# tarocco-v1_1.net
KiCad netlist of a schematic drawn in EAGLE
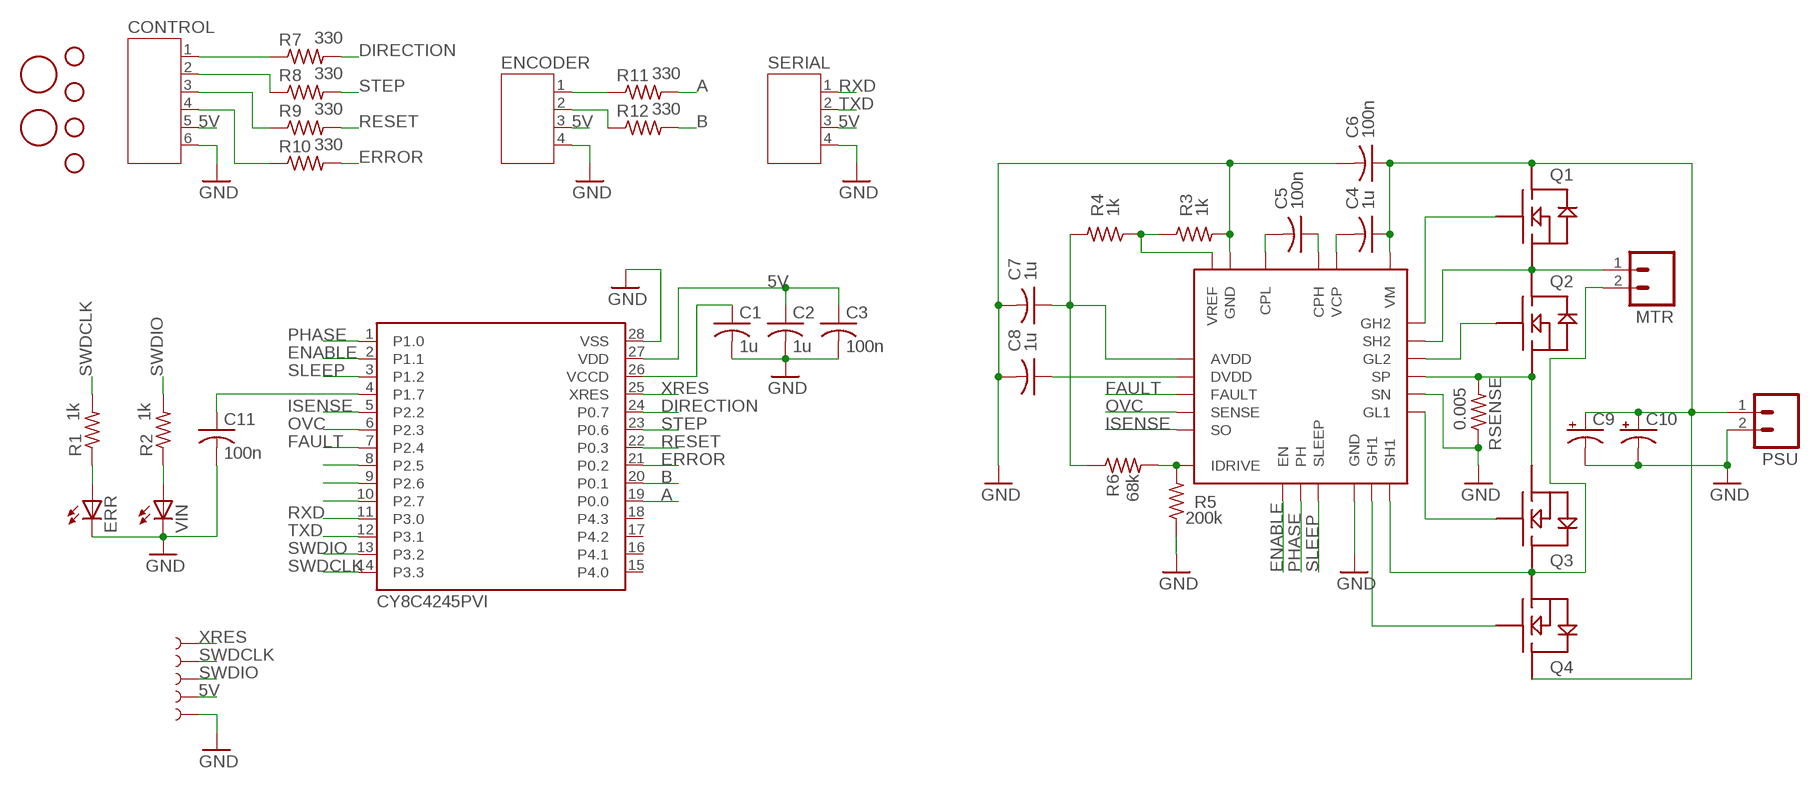
[diagram p0: schematic, sheet 1]

(export (version "E")
  (design (tool "Eeschema 10.0.6"))
  (components
    (comp (ref "8701")
      (value "DRV8701")
      (footprint "eagle-import:VQFN24")
      (libsource (lib "eagle-import") (part "DRV8701"))
    )
    (comp (ref "C1")
      (value "1u")
      (footprint "eagle-import:C0603")
      (libsource (lib "eagle-import") (part "C-USC0603"))
    )
    (comp (ref "C2")
      (value "1u")
      (footprint "eagle-import:C0603")
      (libsource (lib "eagle-import") (part "C-USC0603"))
    )
    (comp (ref "C3")
      (value "100n")
      (footprint "eagle-import:C0603")
      (libsource (lib "eagle-import") (part "C-USC0603"))
    )
    (comp (ref "C4")
      (value "1u")
      (footprint "eagle-import:C0603")
      (libsource (lib "eagle-import") (part "C-USC0603"))
    )
    (comp (ref "C5")
      (value "100n")
      (footprint "eagle-import:C0603")
      (libsource (lib "eagle-import") (part "C-USC0603"))
    )
    (comp (ref "C6")
      (value "100n")
      (footprint "eagle-import:C0603")
      (libsource (lib "eagle-import") (part "C-USC0603"))
    )
    (comp (ref "C7")
      (value "1u")
      (footprint "eagle-import:C0603")
      (libsource (lib "eagle-import") (part "C-USC0603"))
    )
    (comp (ref "C8")
      (value "1u")
      (footprint "eagle-import:C0603")
      (libsource (lib "eagle-import") (part "C-USC0603"))
    )
    (comp (ref "C9")
      (value "CPOL-USE3.5-8")
      (footprint "eagle-import:E3,5-8")
      (libsource (lib "eagle-import") (part "CPOL-USE3.5-8"))
    )
    (comp (ref "C10")
      (value "CPOL-USE3.5-8")
      (footprint "eagle-import:E3,5-8")
      (libsource (lib "eagle-import") (part "CPOL-USE3.5-8"))
    )
    (comp (ref "C11")
      (value "100n")
      (footprint "eagle-import:C0603")
      (libsource (lib "eagle-import") (part "C-USC0603"))
    )
    (comp (ref "CONTROL")
      (value "JST-PH6")
      (footprint "eagle-import:JST-PH6")
      (libsource (lib "eagle-import") (part "JST-PH6"))
    )
    (comp (ref "ENCODER")
      (value "JST-PH4")
      (footprint "eagle-import:JST-PH4")
      (libsource (lib "eagle-import") (part "JST-PH4"))
    )
    (comp (ref "ERR")
      (value "LEDCHIP-LED0603")
      (footprint "eagle-import:CHIP-LED0603")
      (libsource (lib "eagle-import") (part "LEDCHIP-LED0603"))
    )
    (comp (ref "IC1")
      (value "CY8C4545PVI")
      (footprint "eagle-import:SSOP28")
      (libsource (lib "eagle-import") (part "CY8C4545PVI"))
    )
    (comp (ref "MTR")
      (value "M023.5MM")
      (footprint "eagle-import:SCREWTERMINAL-3.5MM-2")
      (libsource (lib "eagle-import") (part "M023.5MM"))
    )
    (comp (ref "PSU")
      (value "M023.5MM")
      (footprint "eagle-import:SCREWTERMINAL-3.5MM-2")
      (libsource (lib "eagle-import") (part "M023.5MM"))
    )
    (comp (ref "Q1")
      (value "NEXFET_SINGLECSD18537NQ5A")
      (footprint "eagle-import:SON5X6")
      (libsource (lib "eagle-import") (part "NEXFET_SINGLECSD18537NQ5A"))
    )
    (comp (ref "Q2")
      (value "NEXFET_SINGLECSD18537NQ5A")
      (footprint "eagle-import:SON5X6")
      (libsource (lib "eagle-import") (part "NEXFET_SINGLECSD18537NQ5A"))
    )
    (comp (ref "Q3")
      (value "NEXFET_SINGLECSD18537NQ5A")
      (footprint "eagle-import:SON5X6")
      (libsource (lib "eagle-import") (part "NEXFET_SINGLECSD18537NQ5A"))
    )
    (comp (ref "Q4")
      (value "NEXFET_SINGLECSD18537NQ5A")
      (footprint "eagle-import:SON5X6")
      (libsource (lib "eagle-import") (part "NEXFET_SINGLECSD18537NQ5A"))
    )
    (comp (ref "R1")
      (value "1k")
      (footprint "eagle-import:R0603")
      (libsource (lib "eagle-import") (part "R-US_R0603"))
    )
    (comp (ref "R2")
      (value "1k")
      (footprint "eagle-import:R0603")
      (libsource (lib "eagle-import") (part "R-US_R0603"))
    )
    (comp (ref "R3")
      (value "1k")
      (footprint "eagle-import:R0603")
      (libsource (lib "eagle-import") (part "R-US_R0603"))
    )
    (comp (ref "R4")
      (value "1k")
      (footprint "eagle-import:R0603")
      (libsource (lib "eagle-import") (part "R-US_R0603"))
    )
    (comp (ref "R5")
      (value "200k")
      (footprint "eagle-import:R0603")
      (libsource (lib "eagle-import") (part "R-US_R0603"))
    )
    (comp (ref "R6")
      (value "68k")
      (footprint "eagle-import:R0603")
      (libsource (lib "eagle-import") (part "R-US_R0603"))
    )
    (comp (ref "R7")
      (value "330")
      (footprint "eagle-import:R0603")
      (libsource (lib "eagle-import") (part "R-US_R0603"))
    )
    (comp (ref "R8")
      (value "330")
      (footprint "eagle-import:R0603")
      (libsource (lib "eagle-import") (part "R-US_R0603"))
    )
    (comp (ref "R9")
      (value "330")
      (footprint "eagle-import:R0603")
      (libsource (lib "eagle-import") (part "R-US_R0603"))
    )
    (comp (ref "R10")
      (value "330")
      (footprint "eagle-import:R0603")
      (libsource (lib "eagle-import") (part "R-US_R0603"))
    )
    (comp (ref "R11")
      (value "330")
      (footprint "eagle-import:R0603")
      (libsource (lib "eagle-import") (part "R-US_R0603"))
    )
    (comp (ref "R12")
      (value "330")
      (footprint "eagle-import:R0603")
      (libsource (lib "eagle-import") (part "R-US_R0603"))
    )
    (comp (ref "RSENSE")
      (value "0.005")
      (footprint "eagle-import:R2512")
      (libsource (lib "eagle-import") (part "R-US_R2512"))
    )
    (comp (ref "SERIAL")
      (value "JST-PH4")
      (footprint "eagle-import:JST-PH4")
      (libsource (lib "eagle-import") (part "JST-PH4"))
    )
    (comp (ref "STANDOFF1")
      (value "STAND-OFF")
      (footprint "eagle-import:STAND-OFF")
      (libsource (lib "eagle-import") (part "STAND-OFF"))
    )
    (comp (ref "STANDOFF2")
      (value "STAND-OFF")
      (footprint "eagle-import:STAND-OFF")
      (libsource (lib "eagle-import") (part "STAND-OFF"))
    )
    (comp (ref "STANDOFF3")
      (value "STAND-OFF")
      (footprint "eagle-import:STAND-OFF")
      (libsource (lib "eagle-import") (part "STAND-OFF"))
    )
    (comp (ref "STANDOFF4")
      (value "STAND-OFF")
      (footprint "eagle-import:STAND-OFF")
      (libsource (lib "eagle-import") (part "STAND-OFF"))
    )
    (comp (ref "TP1")
      (value "TEST-POINT3X5")
      (footprint "eagle-import:PAD.03X.05")
      (libsource (lib "eagle-import") (part "TEST-POINT3X5"))
    )
    (comp (ref "TP2")
      (value "TEST-POINT3X5")
      (footprint "eagle-import:PAD.03X.05")
      (libsource (lib "eagle-import") (part "TEST-POINT3X5"))
    )
    (comp (ref "TP3")
      (value "TEST-POINT3X5")
      (footprint "eagle-import:PAD.03X.05")
      (libsource (lib "eagle-import") (part "TEST-POINT3X5"))
    )
    (comp (ref "TP4")
      (value "TEST-POINT3X5")
      (footprint "eagle-import:PAD.03X.05")
      (libsource (lib "eagle-import") (part "TEST-POINT3X5"))
    )
    (comp (ref "TP5")
      (value "TEST-POINT3X5")
      (footprint "eagle-import:PAD.03X.05")
      (libsource (lib "eagle-import") (part "TEST-POINT3X5"))
    )
    (comp (ref "U$1")
      (value "FIDUCIAL")
      (footprint "eagle-import:FIDUCIAL_1MM")
      (libsource (lib "eagle-import") (part "FIDUCIAL"))
    )
    (comp (ref "U$3")
      (value "FIDUCIAL")
      (footprint "eagle-import:FIDUCIAL_1MM")
      (libsource (lib "eagle-import") (part "FIDUCIAL"))
    )
    (comp (ref "VIN")
      (value "LEDCHIP-LED0603")
      (footprint "eagle-import:CHIP-LED0603")
      (libsource (lib "eagle-import") (part "LEDCHIP-LED0603"))
    )
  )
  (nets
    (net (code "1") (name "/5V") (class "Default")
      (node (ref "C2") (pin "1") (pinfunction "1_1") (pintype "passive"))
      (node (ref "C3") (pin "1") (pinfunction "1_1") (pintype "passive"))
      (node (ref "CONTROL") (pin "5") (pinfunction "5_5") (pintype "passive"))
      (node (ref "ENCODER") (pin "3") (pinfunction "3_3") (pintype "passive"))
      (node (ref "IC1") (pin "27") (pinfunction "VDD_27") (pintype "power_in"))
      (node (ref "SERIAL") (pin "3") (pinfunction "3_3") (pintype "passive"))
      (node (ref "TP4") (pin "P$1") (pinfunction "1_P$1") (pintype "bidirectional"))
    )
    (net (code "2") (name "/A") (class "Default")
      (node (ref "IC1") (pin "19") (pinfunction "P0.0_19") (pintype "bidirectional"))
      (node (ref "R11") (pin "2") (pinfunction "2_2") (pintype "passive"))
    )
    (net (code "3") (name "/B") (class "Default")
      (node (ref "IC1") (pin "20") (pinfunction "P0.1_20") (pintype "bidirectional"))
      (node (ref "R12") (pin "2") (pinfunction "2_2") (pintype "passive"))
    )
    (net (code "4") (name "/DIRECTION") (class "Default")
      (node (ref "IC1") (pin "24") (pinfunction "P0.7_24") (pintype "bidirectional"))
      (node (ref "R7") (pin "2") (pinfunction "2_2") (pintype "passive"))
    )
    (net (code "5") (name "/ENABLE") (class "Default")
      (node (ref "8701") (pin "EN") (pinfunction "EN_EN") (pintype "bidirectional"))
      (node (ref "IC1") (pin "2") (pinfunction "P1.1_2") (pintype "bidirectional"))
    )
    (net (code "6") (name "/ERROR") (class "Default")
      (node (ref "IC1") (pin "21") (pinfunction "P0.2_21") (pintype "bidirectional"))
      (node (ref "R10") (pin "2") (pinfunction "2_2") (pintype "passive"))
    )
    (net (code "7") (name "/FAULT") (class "Default")
      (node (ref "8701") (pin "FAULT") (pinfunction "FAULT_FAULT") (pintype "bidirectional"))
      (node (ref "IC1") (pin "7") (pinfunction "P2.4_7") (pintype "bidirectional"))
    )
    (net (code "8") (name "/ISENSE") (class "Default")
      (node (ref "8701") (pin "SO") (pinfunction "SO_SO") (pintype "bidirectional"))
      (node (ref "IC1") (pin "5") (pinfunction "P2.2_5") (pintype "bidirectional"))
    )
    (net (code "9") (name "/OVC") (class "Default")
      (node (ref "8701") (pin "SENSE") (pinfunction "SENSE_SENSE") (pintype "bidirectional"))
      (node (ref "IC1") (pin "6") (pinfunction "P2.3_6") (pintype "bidirectional"))
    )
    (net (code "10") (name "/PHASE") (class "Default")
      (node (ref "8701") (pin "PH") (pinfunction "PH_PH") (pintype "bidirectional"))
      (node (ref "IC1") (pin "1") (pinfunction "P1.0_1") (pintype "bidirectional"))
    )
    (net (code "11") (name "/RESET") (class "Default")
      (node (ref "IC1") (pin "22") (pinfunction "P0.3_22") (pintype "bidirectional"))
      (node (ref "R9") (pin "2") (pinfunction "2_2") (pintype "passive"))
    )
    (net (code "12") (name "/RXD") (class "Default")
      (node (ref "IC1") (pin "11") (pinfunction "P3.0_11") (pintype "bidirectional"))
      (node (ref "SERIAL") (pin "1") (pinfunction "1_1") (pintype "passive"))
    )
    (net (code "13") (name "/SLEEP") (class "Default")
      (node (ref "8701") (pin "SLEEP") (pinfunction "SLEEP_SLEEP") (pintype "bidirectional"))
      (node (ref "IC1") (pin "3") (pinfunction "P1.2_3") (pintype "bidirectional"))
    )
    (net (code "14") (name "/STEP") (class "Default")
      (node (ref "IC1") (pin "23") (pinfunction "P0.6_23") (pintype "bidirectional"))
      (node (ref "R8") (pin "2") (pinfunction "2_2") (pintype "passive"))
    )
    (net (code "15") (name "/SWDCLK") (class "Default")
      (node (ref "IC1") (pin "14") (pinfunction "P3.3_14") (pintype "bidirectional"))
      (node (ref "R1") (pin "2") (pinfunction "2_2") (pintype "passive"))
      (node (ref "TP2") (pin "P$1") (pinfunction "1_P$1") (pintype "bidirectional"))
    )
    (net (code "16") (name "/SWDIO") (class "Default")
      (node (ref "IC1") (pin "13") (pinfunction "P3.2_13") (pintype "bidirectional"))
      (node (ref "R2") (pin "2") (pinfunction "2_2") (pintype "passive"))
      (node (ref "TP3") (pin "P$1") (pinfunction "1_P$1") (pintype "bidirectional"))
    )
    (net (code "17") (name "/TXD") (class "Default")
      (node (ref "IC1") (pin "12") (pinfunction "P3.1_12") (pintype "bidirectional"))
      (node (ref "SERIAL") (pin "2") (pinfunction "2_2") (pintype "passive"))
    )
    (net (code "18") (name "/XRES") (class "Default")
      (node (ref "IC1") (pin "25") (pinfunction "XRES_25") (pintype "bidirectional"))
      (node (ref "TP1") (pin "P$1") (pinfunction "1_P$1") (pintype "bidirectional"))
    )
    (net (code "19") (name "GND") (class "Default")
      (node (ref "8701") (pin "GND@1") (pinfunction "GND_GND@1") (pintype "bidirectional"))
      (node (ref "8701") (pin "GND@2") (pinfunction "GND_GND@2") (pintype "bidirectional"))
      (node (ref "8701") (pin "GND@3") (pinfunction "GND_GND@3") (pintype "bidirectional"))
      (node (ref "8701") (pin "SN") (pinfunction "SN_SN") (pintype "bidirectional"))
      (node (ref "C1") (pin "2") (pinfunction "2_2") (pintype "passive"))
      (node (ref "C10") (pin "-") (pinfunction "-_-") (pintype "passive"))
      (node (ref "C11") (pin "2") (pinfunction "2_2") (pintype "passive"))
      (node (ref "C2") (pin "2") (pinfunction "2_2") (pintype "passive"))
      (node (ref "C3") (pin "2") (pinfunction "2_2") (pintype "passive"))
      (node (ref "C6") (pin "2") (pinfunction "2_2") (pintype "passive"))
      (node (ref "C7") (pin "2") (pinfunction "2_2") (pintype "passive"))
      (node (ref "C8") (pin "2") (pinfunction "2_2") (pintype "passive"))
      (node (ref "C9") (pin "-") (pinfunction "-_-") (pintype "passive"))
      (node (ref "CONTROL") (pin "6") (pinfunction "6_6") (pintype "passive"))
      (node (ref "ENCODER") (pin "4") (pinfunction "4_4") (pintype "passive"))
      (node (ref "ERR") (pin "C") (pinfunction "C_C") (pintype "passive"))
      (node (ref "IC1") (pin "28") (pinfunction "VSS_28") (pintype "power_in"))
      (node (ref "PSU") (pin "2") (pinfunction "2_2") (pintype "passive"))
      (node (ref "R3") (pin "2") (pinfunction "2_2") (pintype "passive"))
      (node (ref "R5") (pin "1") (pinfunction "1_1") (pintype "passive"))
      (node (ref "RSENSE") (pin "1") (pinfunction "1_1") (pintype "passive"))
      (node (ref "SERIAL") (pin "4") (pinfunction "4_4") (pintype "passive"))
      (node (ref "TP5") (pin "P$1") (pinfunction "1_P$1") (pintype "bidirectional"))
      (node (ref "VIN") (pin "C") (pinfunction "C_C") (pintype "passive"))
    )
    (net (code "20") (name "Net-(8701-PadAVDD)") (class "Default")
      (node (ref "8701") (pin "AVDD") (pinfunction "AVDD_AVDD") (pintype "bidirectional"))
      (node (ref "C7") (pin "1") (pinfunction "1_1") (pintype "passive"))
      (node (ref "R4") (pin "2") (pinfunction "2_2") (pintype "passive"))
      (node (ref "R6") (pin "1") (pinfunction "1_1") (pintype "passive"))
    )
    (net (code "21") (name "Net-(8701-PadCPH)") (class "Default")
      (node (ref "8701") (pin "CPH") (pinfunction "CPH_CPH") (pintype "bidirectional"))
      (node (ref "C5") (pin "1") (pinfunction "1_1") (pintype "passive"))
    )
    (net (code "22") (name "Net-(8701-PadCPL)") (class "Default")
      (node (ref "8701") (pin "CPL") (pinfunction "CPL_CPL") (pintype "bidirectional"))
      (node (ref "C5") (pin "2") (pinfunction "2_2") (pintype "passive"))
    )
    (net (code "23") (name "Net-(8701-PadDVDD)") (class "Default")
      (node (ref "8701") (pin "DVDD") (pinfunction "DVDD_DVDD") (pintype "bidirectional"))
      (node (ref "C8") (pin "1") (pinfunction "1_1") (pintype "passive"))
    )
    (net (code "24") (name "Net-(8701-PadGH1)") (class "Default")
      (node (ref "8701") (pin "GH1") (pinfunction "GH1_GH1") (pintype "bidirectional"))
      (node (ref "Q4") (pin "GATE") (pinfunction "GATE_GATE") (pintype "bidirectional"))
    )
    (net (code "25") (name "Net-(8701-PadGH2)") (class "Default")
      (node (ref "8701") (pin "GH2") (pinfunction "GH2_GH2") (pintype "bidirectional"))
      (node (ref "Q1") (pin "GATE") (pinfunction "GATE_GATE") (pintype "bidirectional"))
    )
    (net (code "26") (name "Net-(8701-PadGL1)") (class "Default")
      (node (ref "8701") (pin "GL1") (pinfunction "GL1_GL1") (pintype "bidirectional"))
      (node (ref "Q3") (pin "GATE") (pinfunction "GATE_GATE") (pintype "bidirectional"))
    )
    (net (code "27") (name "Net-(8701-PadGL2)") (class "Default")
      (node (ref "8701") (pin "GL2") (pinfunction "GL2_GL2") (pintype "bidirectional"))
      (node (ref "Q2") (pin "GATE") (pinfunction "GATE_GATE") (pintype "bidirectional"))
    )
    (net (code "28") (name "Net-(8701-PadIDRIVE)") (class "Default")
      (node (ref "8701") (pin "IDRIVE") (pinfunction "IDRIVE_IDRIVE") (pintype "bidirectional"))
      (node (ref "R5") (pin "2") (pinfunction "2_2") (pintype "passive"))
      (node (ref "R6") (pin "2") (pinfunction "2_2") (pintype "passive"))
    )
    (net (code "29") (name "Net-(8701-PadSH1)") (class "Default")
      (node (ref "8701") (pin "SH1") (pinfunction "SH1_SH1") (pintype "bidirectional"))
      (node (ref "MTR") (pin "2") (pinfunction "2_2") (pintype "passive"))
      (node (ref "Q3") (pin "DRAIN@1") (pinfunction "DRAIN_DRAIN@1") (pintype "bidirectional"))
      (node (ref "Q3") (pin "DRAIN@2") (pinfunction "DRAIN_DRAIN@2") (pintype "bidirectional"))
      (node (ref "Q3") (pin "DRAIN@3") (pinfunction "DRAIN_DRAIN@3") (pintype "bidirectional"))
      (node (ref "Q3") (pin "DRAIN@4") (pinfunction "DRAIN_DRAIN@4") (pintype "bidirectional"))
      (node (ref "Q3") (pin "DRAIN@5") (pinfunction "DRAIN_DRAIN@5") (pintype "bidirectional"))
      (node (ref "Q4") (pin "SOURCE@1") (pinfunction "SOURCE_SOURCE@1") (pintype "bidirectional"))
      (node (ref "Q4") (pin "SOURCE@2") (pinfunction "SOURCE_SOURCE@2") (pintype "bidirectional"))
      (node (ref "Q4") (pin "SOURCE@3") (pinfunction "SOURCE_SOURCE@3") (pintype "bidirectional"))
    )
    (net (code "30") (name "Net-(8701-PadSH2)") (class "Default")
      (node (ref "8701") (pin "SH2") (pinfunction "SH2_SH2") (pintype "bidirectional"))
      (node (ref "MTR") (pin "1") (pinfunction "1_1") (pintype "passive"))
      (node (ref "Q1") (pin "SOURCE@1") (pinfunction "SOURCE_SOURCE@1") (pintype "bidirectional"))
      (node (ref "Q1") (pin "SOURCE@2") (pinfunction "SOURCE_SOURCE@2") (pintype "bidirectional"))
      (node (ref "Q1") (pin "SOURCE@3") (pinfunction "SOURCE_SOURCE@3") (pintype "bidirectional"))
      (node (ref "Q2") (pin "DRAIN@1") (pinfunction "DRAIN_DRAIN@1") (pintype "bidirectional"))
      (node (ref "Q2") (pin "DRAIN@2") (pinfunction "DRAIN_DRAIN@2") (pintype "bidirectional"))
      (node (ref "Q2") (pin "DRAIN@3") (pinfunction "DRAIN_DRAIN@3") (pintype "bidirectional"))
      (node (ref "Q2") (pin "DRAIN@4") (pinfunction "DRAIN_DRAIN@4") (pintype "bidirectional"))
      (node (ref "Q2") (pin "DRAIN@5") (pinfunction "DRAIN_DRAIN@5") (pintype "bidirectional"))
    )
    (net (code "31") (name "Net-(8701-PadSP)") (class "Default")
      (node (ref "8701") (pin "SP") (pinfunction "SP_SP") (pintype "bidirectional"))
      (node (ref "Q2") (pin "SOURCE@1") (pinfunction "SOURCE_SOURCE@1") (pintype "bidirectional"))
      (node (ref "Q2") (pin "SOURCE@2") (pinfunction "SOURCE_SOURCE@2") (pintype "bidirectional"))
      (node (ref "Q2") (pin "SOURCE@3") (pinfunction "SOURCE_SOURCE@3") (pintype "bidirectional"))
      (node (ref "Q3") (pin "SOURCE@1") (pinfunction "SOURCE_SOURCE@1") (pintype "bidirectional"))
      (node (ref "Q3") (pin "SOURCE@2") (pinfunction "SOURCE_SOURCE@2") (pintype "bidirectional"))
      (node (ref "Q3") (pin "SOURCE@3") (pinfunction "SOURCE_SOURCE@3") (pintype "bidirectional"))
      (node (ref "RSENSE") (pin "2") (pinfunction "2_2") (pintype "passive"))
    )
    (net (code "32") (name "Net-(8701-PadVCP)") (class "Default")
      (node (ref "8701") (pin "VCP") (pinfunction "VCP_VCP") (pintype "bidirectional"))
      (node (ref "C4") (pin "2") (pinfunction "2_2") (pintype "passive"))
    )
    (net (code "33") (name "Net-(8701-PadVM)") (class "Default")
      (node (ref "8701") (pin "VM") (pinfunction "VM_VM") (pintype "bidirectional"))
      (node (ref "C10") (pin "+") (pinfunction "+_+") (pintype "passive"))
      (node (ref "C4") (pin "1") (pinfunction "1_1") (pintype "passive"))
      (node (ref "C6") (pin "1") (pinfunction "1_1") (pintype "passive"))
      (node (ref "C9") (pin "+") (pinfunction "+_+") (pintype "passive"))
      (node (ref "PSU") (pin "1") (pinfunction "1_1") (pintype "passive"))
      (node (ref "Q1") (pin "DRAIN@1") (pinfunction "DRAIN_DRAIN@1") (pintype "bidirectional"))
      (node (ref "Q1") (pin "DRAIN@2") (pinfunction "DRAIN_DRAIN@2") (pintype "bidirectional"))
      (node (ref "Q1") (pin "DRAIN@3") (pinfunction "DRAIN_DRAIN@3") (pintype "bidirectional"))
      (node (ref "Q1") (pin "DRAIN@4") (pinfunction "DRAIN_DRAIN@4") (pintype "bidirectional"))
      (node (ref "Q1") (pin "DRAIN@5") (pinfunction "DRAIN_DRAIN@5") (pintype "bidirectional"))
      (node (ref "Q4") (pin "DRAIN@1") (pinfunction "DRAIN_DRAIN@1") (pintype "bidirectional"))
      (node (ref "Q4") (pin "DRAIN@2") (pinfunction "DRAIN_DRAIN@2") (pintype "bidirectional"))
      (node (ref "Q4") (pin "DRAIN@3") (pinfunction "DRAIN_DRAIN@3") (pintype "bidirectional"))
      (node (ref "Q4") (pin "DRAIN@4") (pinfunction "DRAIN_DRAIN@4") (pintype "bidirectional"))
      (node (ref "Q4") (pin "DRAIN@5") (pinfunction "DRAIN_DRAIN@5") (pintype "bidirectional"))
    )
    (net (code "34") (name "Net-(8701-PadVREF)") (class "Default")
      (node (ref "8701") (pin "VREF") (pinfunction "VREF_VREF") (pintype "bidirectional"))
      (node (ref "R3") (pin "1") (pinfunction "1_1") (pintype "passive"))
      (node (ref "R4") (pin "1") (pinfunction "1_1") (pintype "passive"))
    )
    (net (code "35") (name "Net-(CONTROL-Pad1)") (class "Default")
      (node (ref "CONTROL") (pin "1") (pinfunction "1_1") (pintype "passive"))
      (node (ref "R7") (pin "1") (pinfunction "1_1") (pintype "passive"))
    )
    (net (code "36") (name "Net-(CONTROL-Pad2)") (class "Default")
      (node (ref "CONTROL") (pin "2") (pinfunction "2_2") (pintype "passive"))
      (node (ref "R8") (pin "1") (pinfunction "1_1") (pintype "passive"))
    )
    (net (code "37") (name "Net-(CONTROL-Pad3)") (class "Default")
      (node (ref "CONTROL") (pin "3") (pinfunction "3_3") (pintype "passive"))
      (node (ref "R9") (pin "1") (pinfunction "1_1") (pintype "passive"))
    )
    (net (code "38") (name "Net-(CONTROL-Pad4)") (class "Default")
      (node (ref "CONTROL") (pin "4") (pinfunction "4_4") (pintype "passive"))
      (node (ref "R10") (pin "1") (pinfunction "1_1") (pintype "passive"))
    )
    (net (code "39") (name "Net-(ENCODER-Pad1)") (class "Default")
      (node (ref "ENCODER") (pin "1") (pinfunction "1_1") (pintype "passive"))
      (node (ref "R11") (pin "1") (pinfunction "1_1") (pintype "passive"))
    )
    (net (code "40") (name "Net-(ENCODER-Pad2)") (class "Default")
      (node (ref "ENCODER") (pin "2") (pinfunction "2_2") (pintype "passive"))
      (node (ref "R12") (pin "1") (pinfunction "1_1") (pintype "passive"))
    )
    (net (code "41") (name "Net-(ERR-PadA)") (class "Default")
      (node (ref "ERR") (pin "A") (pinfunction "A_A") (pintype "passive"))
      (node (ref "R1") (pin "1") (pinfunction "1_1") (pintype "passive"))
    )
    (net (code "42") (name "Net-(IC1-P1.7)") (class "Default")
      (node (ref "C11") (pin "1") (pinfunction "1_1") (pintype "passive"))
      (node (ref "IC1") (pin "4") (pinfunction "P1.7_4") (pintype "bidirectional"))
    )
    (net (code "43") (name "Net-(IC1-VCCD)") (class "Default")
      (node (ref "C1") (pin "1") (pinfunction "1_1") (pintype "passive"))
      (node (ref "IC1") (pin "26") (pinfunction "VCCD_26") (pintype "power_in"))
    )
    (net (code "44") (name "Net-(R2-Pad1)") (class "Default")
      (node (ref "R2") (pin "1") (pinfunction "1_1") (pintype "passive"))
      (node (ref "VIN") (pin "A") (pinfunction "A_A") (pintype "passive"))
    )
    (net (code "45") (name "unconnected-(IC1-P2.5-Pad8)") (class "Default")
      (node (ref "IC1") (pin "8") (pinfunction "P2.5_8") (pintype "bidirectional"))
    )
    (net (code "46") (name "unconnected-(IC1-P2.6-Pad9)") (class "Default")
      (node (ref "IC1") (pin "9") (pinfunction "P2.6_9") (pintype "bidirectional"))
    )
    (net (code "47") (name "unconnected-(IC1-P2.7-Pad10)") (class "Default")
      (node (ref "IC1") (pin "10") (pinfunction "P2.7_10") (pintype "bidirectional"))
    )
    (net (code "48") (name "unconnected-(IC1-P4.0-Pad15)") (class "Default")
      (node (ref "IC1") (pin "15") (pinfunction "P4.0_15") (pintype "bidirectional"))
    )
    (net (code "49") (name "unconnected-(IC1-P4.1-Pad16)") (class "Default")
      (node (ref "IC1") (pin "16") (pinfunction "P4.1_16") (pintype "bidirectional"))
    )
    (net (code "50") (name "unconnected-(IC1-P4.2-Pad17)") (class "Default")
      (node (ref "IC1") (pin "17") (pinfunction "P4.2_17") (pintype "bidirectional"))
    )
    (net (code "51") (name "unconnected-(IC1-P4.3-Pad18)") (class "Default")
      (node (ref "IC1") (pin "18") (pinfunction "P4.3_18") (pintype "bidirectional"))
    )
  )
)
